# pcb_4.net
KiCad netlist of a schematic drawn in EAGLE
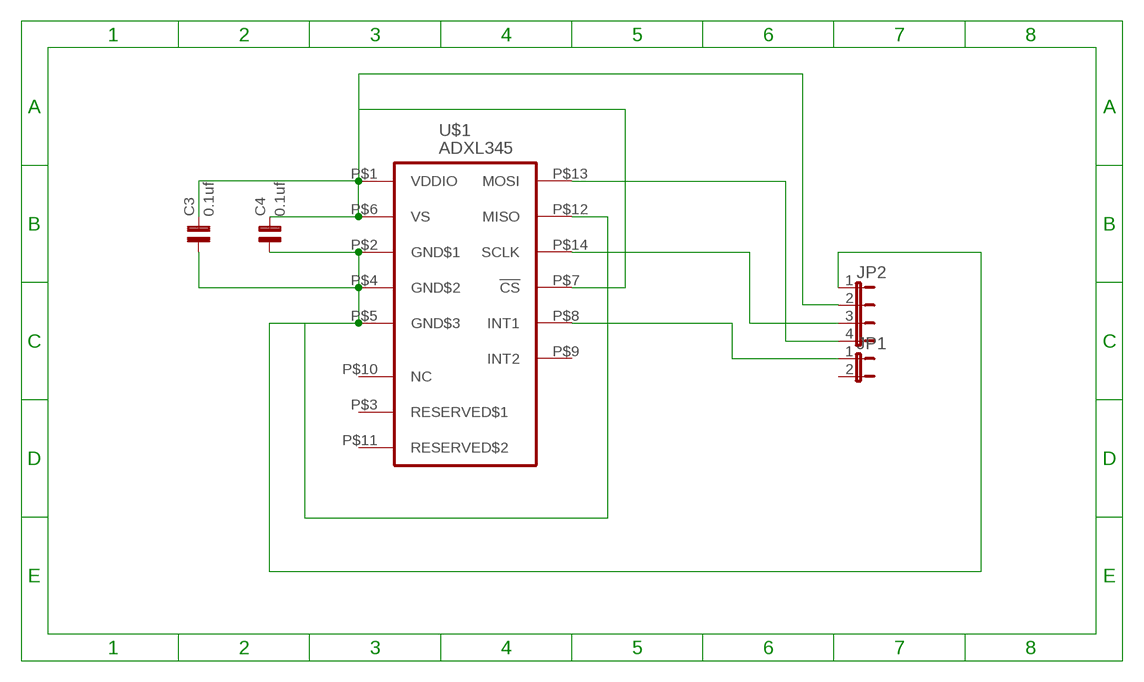
[diagram p0: schematic, sheet 1]

(export (version "E")
  (design (tool "Eeschema 10.0.6"))
  (components
    (comp (ref "C3")
      (value "0.1uf")
      (footprint "eagle-import:0805")
      (libsource (lib "eagle-import") (part "C0805"))
    )
    (comp (ref "C4")
      (value "0.1uf")
      (footprint "eagle-import:0805")
      (libsource (lib "eagle-import") (part "C0805"))
    )
    (comp (ref "JP1")
      (value "JP1E")
      (footprint "eagle-import:JP1")
      (libsource (lib "eagle-import") (part "JP1E"))
    )
    (comp (ref "JP2")
      (value "JP4E")
      (footprint "eagle-import:JP4")
      (libsource (lib "eagle-import") (part "JP4E"))
    )
    (comp (ref "U$1")
      (value "ADXL345")
      (footprint "eagle-import:LGA14")
      (libsource (lib "eagle-import") (part "ADXL345"))
    )
  )
  (nets
    (net (code "1") (name "Net-(U$1-GND$1)") (class "Default")
      (node (ref "C3") (pin "1") (pinfunction "1_1") (pintype "passive"))
      (node (ref "C4") (pin "1") (pinfunction "1_1") (pintype "passive"))
      (node (ref "JP2") (pin "1") (pinfunction "1_1") (pintype "passive"))
      (node (ref "U$1") (pin "P$12") (pinfunction "MISO_P$12") (pintype "output"))
      (node (ref "U$1") (pin "P$2") (pinfunction "GND$1_P$2") (pintype "power_in"))
      (node (ref "U$1") (pin "P$4") (pinfunction "GND$2_P$4") (pintype "power_in"))
      (node (ref "U$1") (pin "P$5") (pinfunction "GND$3_P$5") (pintype "power_in"))
    )
    (net (code "2") (name "Net-(U$1-INT1)") (class "Default")
      (node (ref "JP1") (pin "1") (pinfunction "1_1") (pintype "passive"))
      (node (ref "U$1") (pin "P$8") (pinfunction "INT1_P$8") (pintype "output"))
    )
    (net (code "3") (name "Net-(U$1-MOSI)") (class "Default")
      (node (ref "JP2") (pin "4") (pinfunction "4_4") (pintype "passive"))
      (node (ref "U$1") (pin "P$13") (pinfunction "MOSI_P$13") (pintype "input"))
    )
    (net (code "4") (name "Net-(U$1-SCLK)") (class "Default")
      (node (ref "JP2") (pin "3") (pinfunction "3_3") (pintype "passive"))
      (node (ref "U$1") (pin "P$14") (pinfunction "SCLK_P$14") (pintype "input"))
    )
    (net (code "5") (name "Net-(U$1-VDDIO)") (class "Default")
      (node (ref "C3") (pin "2") (pinfunction "2_2") (pintype "passive"))
      (node (ref "C4") (pin "2") (pinfunction "2_2") (pintype "passive"))
      (node (ref "JP2") (pin "2") (pinfunction "2_2") (pintype "passive"))
      (node (ref "U$1") (pin "P$1") (pinfunction "VDDIO_P$1") (pintype "power_in"))
      (node (ref "U$1") (pin "P$6") (pinfunction "VS_P$6") (pintype "power_in"))
      (node (ref "U$1") (pin "P$7") (pinfunction "~{CS}_P$7") (pintype "input"))
    )
    (net (code "6") (name "unconnected-(JP1-Pad2)") (class "Default")
      (node (ref "JP1") (pin "2") (pinfunction "2_2") (pintype "passive"))
    )
    (net (code "7") (name "unconnected-(U$1-INT2-PadP$9)") (class "Default")
      (node (ref "U$1") (pin "P$9") (pinfunction "INT2_P$9") (pintype "output"))
    )
    (net (code "8") (name "unconnected-(U$1-NC-PadP$10)") (class "Default")
      (node (ref "U$1") (pin "P$10") (pinfunction "NC_P$10") (pintype "bidirectional"))
    )
    (net (code "9") (name "unconnected-(U$1-RESERVED$1-PadP$3)") (class "Default")
      (node (ref "U$1") (pin "P$3") (pinfunction "RESERVED$1_P$3") (pintype "bidirectional"))
    )
    (net (code "10") (name "unconnected-(U$1-RESERVED$2-PadP$11)") (class "Default")
      (node (ref "U$1") (pin "P$11") (pinfunction "RESERVED$2_P$11") (pintype "bidirectional"))
    )
  )
)
